# 2019_FDP_PROPULSION.net
KiCad netlist of a schematic drawn in Altium Designer
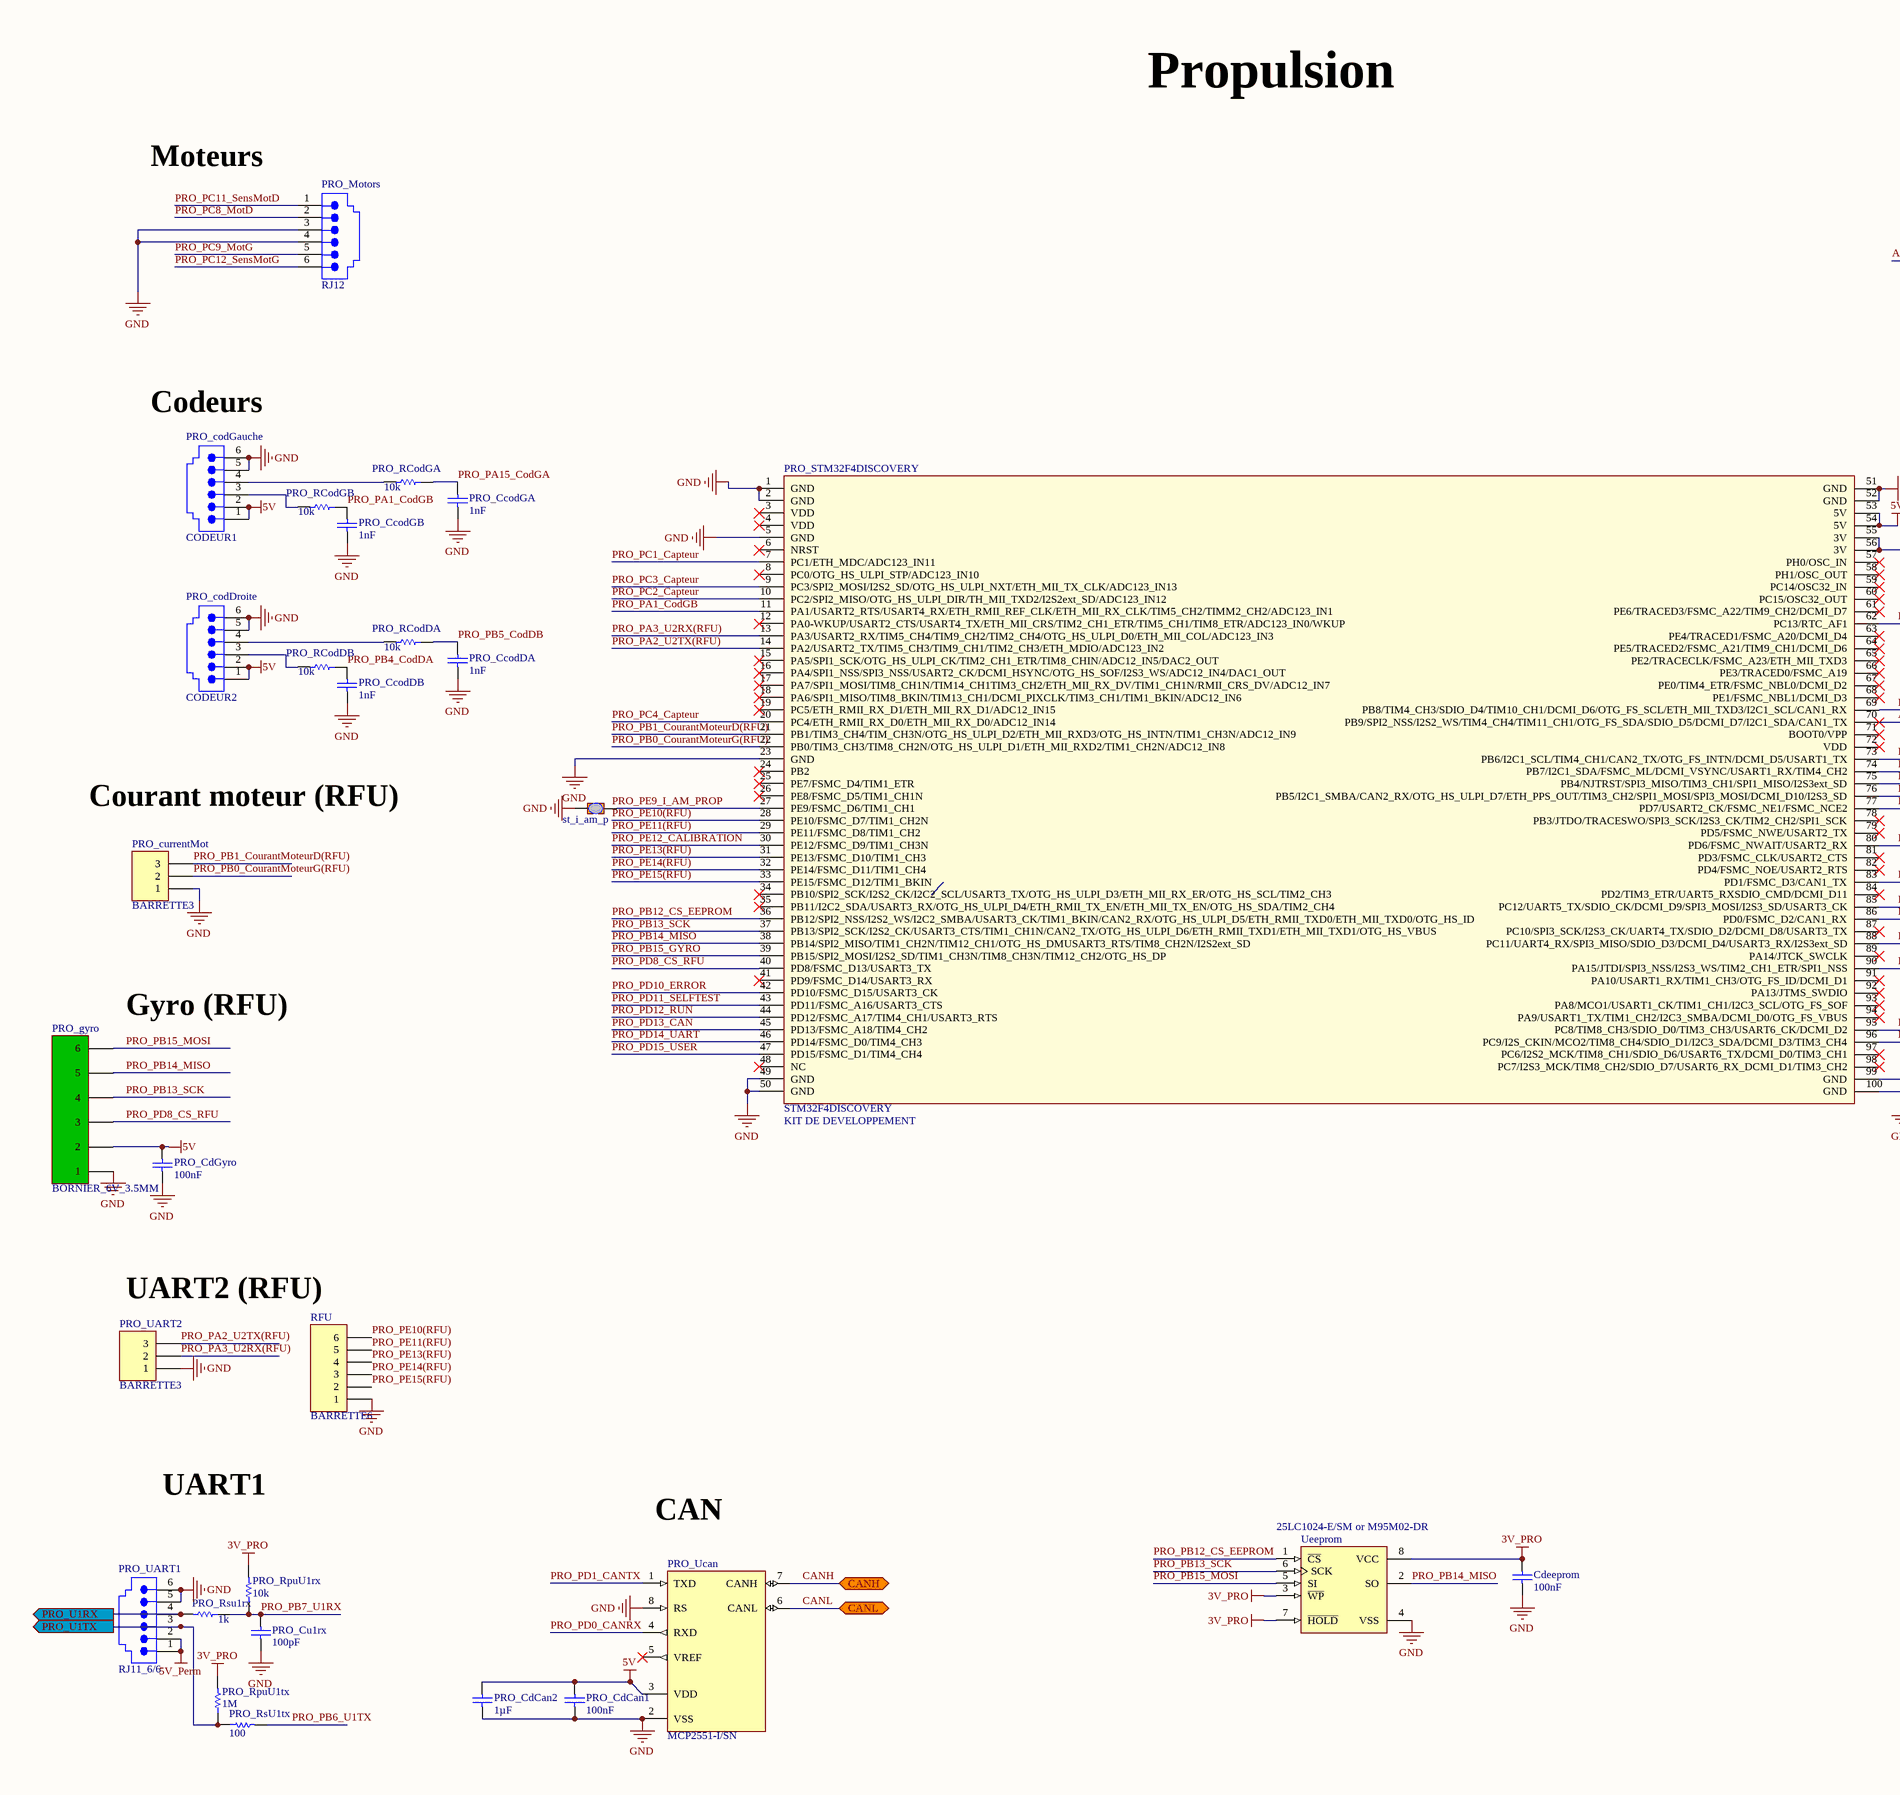
[diagram p0: 2019_FDP_PROPULSION.SchDoc, left]
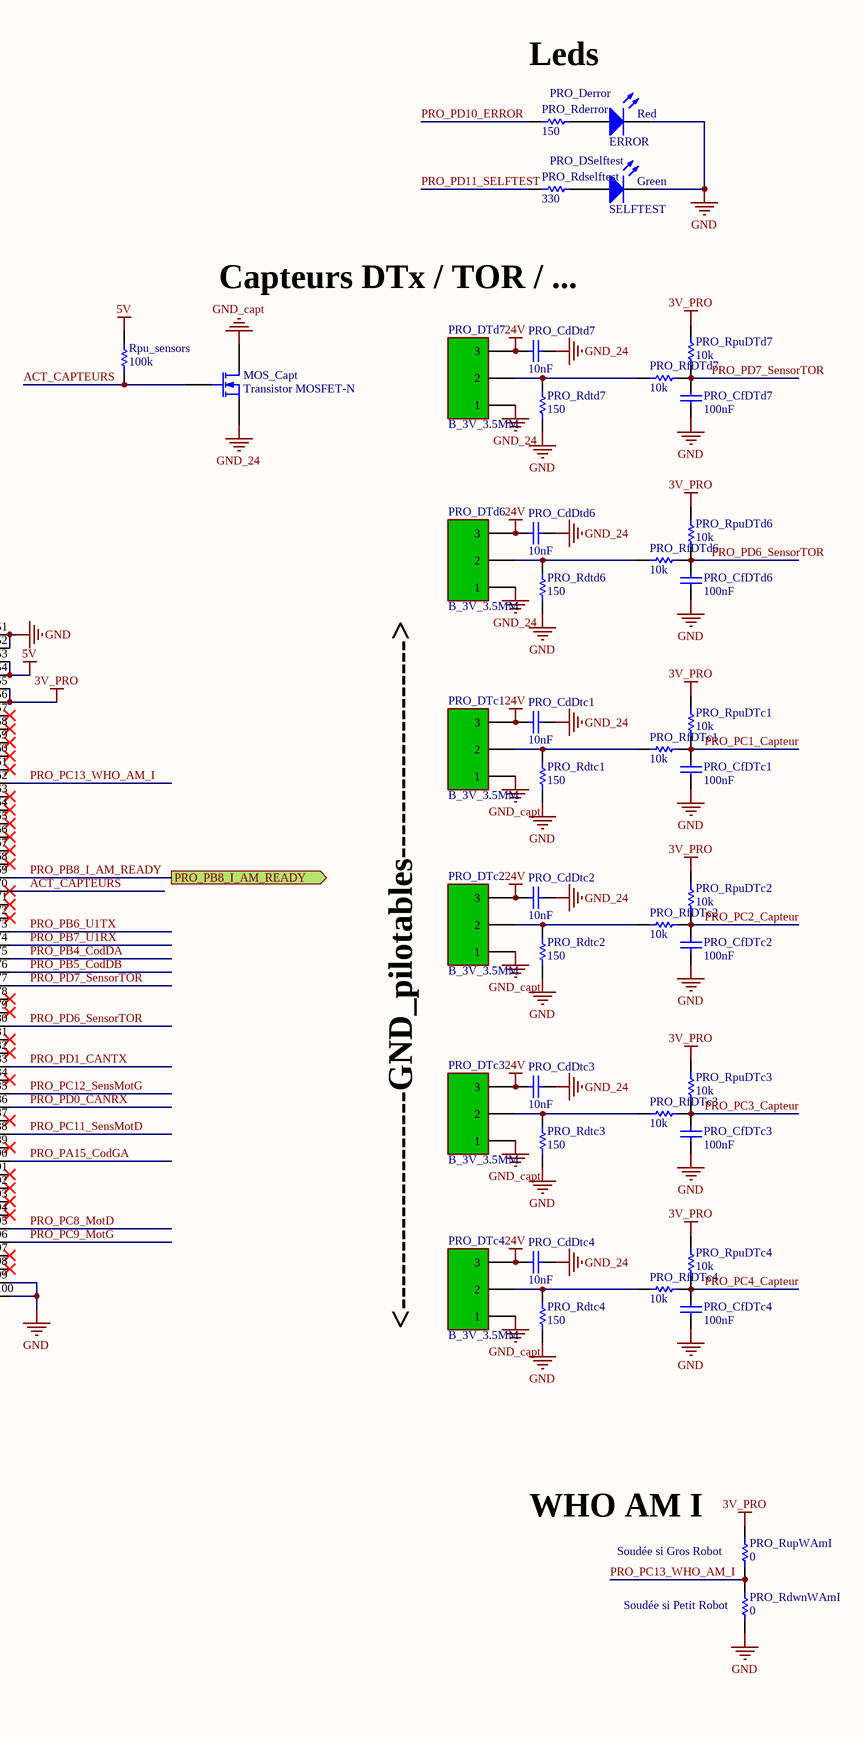
[diagram p1: 2019_FDP_PROPULSION.SchDoc, right]

(export (version "E")
  (design (tool "Eeschema 10.0.6"))
  (components
    (comp (ref "Cdeeprom")
      (value "100nF")
      (footprint "C0805_N")
      (description "Capacitor")
      (fields (field (name "PUBLISHER") "Altium Limited"))
      (libsource (lib "_ROBOT") (part "Condensateur"))
    )
    (comp (ref "MOS_Capt")
      (value "Transistor MOSFET-N")
      (footprint "SOT23-3N")
      (description "N-Channel MOSFET")
      (fields (field (name "PUBLISHER") "Altium Limited"))
      (libsource (lib "_ROBOT") (part "Transistor MOSFET-N"))
    )
    (comp (ref "PRO_CcodDA")
      (value "1nF")
      (footprint "C0805_N")
      (description "Capacitor")
      (fields (field (name "PUBLISHER") "Altium Limited"))
      (libsource (lib "_ROBOT") (part "Condensateur"))
    )
    (comp (ref "PRO_CcodDB")
      (value "1nF")
      (footprint "C0805_N")
      (description "Capacitor")
      (fields (field (name "PUBLISHER") "Altium Limited"))
      (libsource (lib "_ROBOT") (part "Condensateur"))
    )
    (comp (ref "PRO_CcodGA")
      (value "1nF")
      (footprint "C0805_N")
      (description "Capacitor")
      (fields (field (name "PUBLISHER") "Altium Limited"))
      (libsource (lib "_ROBOT") (part "Condensateur"))
    )
    (comp (ref "PRO_CcodGB")
      (value "1nF")
      (footprint "C0805_N")
      (description "Capacitor")
      (fields (field (name "PUBLISHER") "Altium Limited"))
      (libsource (lib "_ROBOT") (part "Condensateur"))
    )
    (comp (ref "PRO_CdCan1")
      (value "100nF")
      (footprint "C0805_N")
      (description "Capacitor")
      (fields (field (name "PUBLISHER") "Altium Limited"))
      (libsource (lib "_ROBOT") (part "Condensateur"))
    )
    (comp (ref "PRO_CdCan2")
      (value "1µF")
      (footprint "C0805_N")
      (description "Capacitor")
      (fields (field (name "PUBLISHER") "Altium Limited"))
      (libsource (lib "_ROBOT") (part "Condensateur"))
    )
    (comp (ref "PRO_CdDtc1")
      (value "10nF")
      (footprint "C0805_N")
      (description "Capacitor")
      (fields (field (name "PUBLISHER") "Altium Limited"))
      (libsource (lib "_ROBOT") (part "Condensateur"))
    )
    (comp (ref "PRO_CdDtc2")
      (value "10nF")
      (footprint "C0805_N")
      (description "Capacitor")
      (fields (field (name "PUBLISHER") "Altium Limited"))
      (libsource (lib "_ROBOT") (part "Condensateur"))
    )
    (comp (ref "PRO_CdDtc3")
      (value "10nF")
      (footprint "C0805_N")
      (description "Capacitor")
      (fields (field (name "PUBLISHER") "Altium Limited"))
      (libsource (lib "_ROBOT") (part "Condensateur"))
    )
    (comp (ref "PRO_CdDtc4")
      (value "10nF")
      (footprint "C0805_N")
      (description "Capacitor")
      (fields (field (name "PUBLISHER") "Altium Limited"))
      (libsource (lib "_ROBOT") (part "Condensateur"))
    )
    (comp (ref "PRO_CdDtd6")
      (value "10nF")
      (footprint "C0805_N")
      (description "Capacitor")
      (fields (field (name "PUBLISHER") "Altium Limited"))
      (libsource (lib "_ROBOT") (part "Condensateur"))
    )
    (comp (ref "PRO_CdDtd7")
      (value "10nF")
      (footprint "C0805_N")
      (description "Capacitor")
      (fields (field (name "PUBLISHER") "Altium Limited"))
      (libsource (lib "_ROBOT") (part "Condensateur"))
    )
    (comp (ref "PRO_CdGyro")
      (value "100nF")
      (footprint "C0805_N")
      (description "Capacitor")
      (fields (field (name "PUBLISHER") "Altium Limited"))
      (libsource (lib "_ROBOT") (part "Condensateur"))
    )
    (comp (ref "PRO_CfDTc1")
      (value "100nF")
      (footprint "C0805_N")
      (description "Capacitor")
      (fields (field (name "PUBLISHER") "Altium Limited"))
      (libsource (lib "_ROBOT") (part "Condensateur"))
    )
    (comp (ref "PRO_CfDTc2")
      (value "100nF")
      (footprint "C0805_N")
      (description "Capacitor")
      (fields (field (name "PUBLISHER") "Altium Limited"))
      (libsource (lib "_ROBOT") (part "Condensateur"))
    )
    (comp (ref "PRO_CfDTc3")
      (value "100nF")
      (footprint "C0805_N")
      (description "Capacitor")
      (fields (field (name "PUBLISHER") "Altium Limited"))
      (libsource (lib "_ROBOT") (part "Condensateur"))
    )
    (comp (ref "PRO_CfDTc4")
      (value "100nF")
      (footprint "C0805_N")
      (description "Capacitor")
      (fields (field (name "PUBLISHER") "Altium Limited"))
      (libsource (lib "_ROBOT") (part "Condensateur"))
    )
    (comp (ref "PRO_CfDTd6")
      (value "100nF")
      (footprint "C0805_N")
      (description "Capacitor")
      (fields (field (name "PUBLISHER") "Altium Limited"))
      (libsource (lib "_ROBOT") (part "Condensateur"))
    )
    (comp (ref "PRO_CfDTd7")
      (value "100nF")
      (footprint "C0805_N")
      (description "Capacitor")
      (fields (field (name "PUBLISHER") "Altium Limited"))
      (libsource (lib "_ROBOT") (part "Condensateur"))
    )
    (comp (ref "PRO_codDroite")
      (value "CODEUR2")
      (footprint "RJ11_6/6 - droit")
      (description "Right Angle, Standard Profile, Offset Latch DECconnect, Flangeless PCB Jack")
      (fields (field (name "PUBLISHER") "Altium Limited"))
      (libsource (lib "miniprojet") (part "RJ11_6/6"))
    )
    (comp (ref "PRO_codGauche")
      (value "CODEUR1")
      (footprint "RJ11_6/6 - droit")
      (description "Right Angle, Standard Profile, Offset Latch DECconnect, Flangeless PCB Jack")
      (fields (field (name "PUBLISHER") "Altium Limited"))
      (libsource (lib "miniprojet") (part "RJ11_6/6"))
    )
    (comp (ref "PRO_Cu1rx")
      (value "100pF")
      (footprint "C0805_N")
      (description "Capacitor")
      (fields (field (name "PUBLISHER") "Altium Limited"))
      (libsource (lib "_ROBOT") (part "Condensateur"))
    )
    (comp (ref "PRO_currentMot")
      (value "BARRETTE3")
      (footprint "HE14_3")
      (description "Header, 3-Pin")
      (fields (field (name "PUBLISHER") "Altium Limited"))
      (libsource (lib "Connecteur") (part "BARRETTE3"))
    )
    (comp (ref "PRO_Derror")
      (value "ERROR")
      (footprint "LED_0805")
      (description "Typical LED")
      (fields (field (name "PUBLISHER") "Altium Limited"))
      (libsource (lib "_ROBOT") (part "LED"))
    )
    (comp (ref "PRO_DSelftest")
      (value "SELFTEST")
      (footprint "LED_0805")
      (description "Typical LED")
      (fields (field (name "PUBLISHER") "Altium Limited"))
      (libsource (lib "_ROBOT") (part "LED"))
    )
    (comp (ref "PRO_DTc1")
      (value "B_3V_3.5MM")
      (footprint "BORNIER_3V_3.5MM")
      (libsource (lib "Connecteur") (part "BORNIER_3V_3.5MM"))
    )
    (comp (ref "PRO_DTc2")
      (value "B_3V_3.5MM")
      (footprint "BORNIER_3V_3.5MM")
      (libsource (lib "Connecteur") (part "BORNIER_3V_3.5MM"))
    )
    (comp (ref "PRO_DTc3")
      (value "B_3V_3.5MM")
      (footprint "BORNIER_3V_3.5MM")
      (libsource (lib "Connecteur") (part "BORNIER_3V_3.5MM"))
    )
    (comp (ref "PRO_DTc4")
      (value "B_3V_3.5MM")
      (footprint "BORNIER_3V_3.5MM")
      (libsource (lib "Connecteur") (part "BORNIER_3V_3.5MM"))
    )
    (comp (ref "PRO_DTd6")
      (value "B_3V_3.5MM")
      (footprint "BORNIER_3V_3.5MM")
      (libsource (lib "Connecteur") (part "BORNIER_3V_3.5MM"))
    )
    (comp (ref "PRO_DTd7")
      (value "B_3V_3.5MM")
      (footprint "BORNIER_3V_3.5MM")
      (libsource (lib "Connecteur") (part "BORNIER_3V_3.5MM"))
    )
    (comp (ref "PRO_gyro")
      (value "BORNIER_6V_3.5MM")
      (footprint "BORNIER_6V_3.5MM")
      (libsource (lib "Connecteur") (part "BORNIER_6V_3.5MM"))
    )
    (comp (ref "PRO_Motors")
      (value "RJ12")
      (footprint "RJ11_6/6 - droit")
      (description "Right Angle, Standard Profile, Offset Latch DECconnect, Flangeless PCB Jack")
      (fields (field (name "PUBLISHER") "Altium Limited"))
      (libsource (lib "Connecteur") (part "RJ11_6/6"))
    )
    (comp (ref "PRO_RCodDA")
      (value "10k")
      (footprint "R1206_N")
      (description "Resistor")
      (fields (field (name "PUBLISHER") "Altium Limited"))
      (libsource (lib "_ROBOT") (part "Resistor"))
    )
    (comp (ref "PRO_RCodDB")
      (value "10k")
      (footprint "R1206_N")
      (description "Resistor")
      (fields (field (name "PUBLISHER") "Altium Limited"))
      (libsource (lib "_ROBOT") (part "Resistor"))
    )
    (comp (ref "PRO_RCodGA")
      (value "10k")
      (footprint "R1206_N")
      (description "Resistor")
      (fields (field (name "PUBLISHER") "Altium Limited"))
      (libsource (lib "_ROBOT") (part "Resistor"))
    )
    (comp (ref "PRO_RCodGB")
      (value "10k")
      (footprint "R1206_N")
      (description "Resistor")
      (fields (field (name "PUBLISHER") "Altium Limited"))
      (libsource (lib "_ROBOT") (part "Resistor"))
    )
    (comp (ref "PRO_Rderror")
      (value "150")
      (footprint "R1206_N")
      (description "Resistor")
      (fields (field (name "PUBLISHER") "Altium Limited"))
      (libsource (lib "_ROBOT") (part "Resistor"))
    )
    (comp (ref "PRO_Rdselftest")
      (value "330")
      (footprint "R1206_N")
      (description "Resistor")
      (fields (field (name "PUBLISHER") "Altium Limited"))
      (libsource (lib "_ROBOT") (part "Resistor"))
    )
    (comp (ref "PRO_Rdtc1")
      (value "150")
      (footprint "R1206_N")
      (description "Resistor")
      (fields (field (name "PUBLISHER") "Altium Limited"))
      (libsource (lib "_ROBOT") (part "Resistor"))
    )
    (comp (ref "PRO_Rdtc2")
      (value "150")
      (footprint "R1206_N")
      (description "Resistor")
      (fields (field (name "PUBLISHER") "Altium Limited"))
      (libsource (lib "_ROBOT") (part "Resistor"))
    )
    (comp (ref "PRO_Rdtc3")
      (value "150")
      (footprint "R1206_N")
      (description "Resistor")
      (fields (field (name "PUBLISHER") "Altium Limited"))
      (libsource (lib "_ROBOT") (part "Resistor"))
    )
    (comp (ref "PRO_Rdtc4")
      (value "150")
      (footprint "R1206_N")
      (description "Resistor")
      (fields (field (name "PUBLISHER") "Altium Limited"))
      (libsource (lib "_ROBOT") (part "Resistor"))
    )
    (comp (ref "PRO_Rdtd6")
      (value "150")
      (footprint "R1206_N")
      (description "Resistor")
      (fields (field (name "PUBLISHER") "Altium Limited"))
      (libsource (lib "_ROBOT") (part "Resistor"))
    )
    (comp (ref "PRO_Rdtd7")
      (value "150")
      (footprint "R1206_N")
      (description "Resistor")
      (fields (field (name "PUBLISHER") "Altium Limited"))
      (libsource (lib "_ROBOT") (part "Resistor"))
    )
    (comp (ref "PRO_RdwnWAmI")
      (value "0")
      (footprint "R1206_N")
      (description "Resistor")
      (fields (field (name "PUBLISHER") "Altium Limited"))
      (libsource (lib "_ROBOT") (part "Resistor"))
    )
    (comp (ref "PRO_RfDTc1")
      (value "10k")
      (footprint "R1206_N")
      (description "Resistor")
      (fields (field (name "PUBLISHER") "Altium Limited"))
      (libsource (lib "_ROBOT") (part "Resistor"))
    )
    (comp (ref "PRO_RfDTc2")
      (value "10k")
      (footprint "R1206_N")
      (description "Resistor")
      (fields (field (name "PUBLISHER") "Altium Limited"))
      (libsource (lib "_ROBOT") (part "Resistor"))
    )
    (comp (ref "PRO_RfDTc3")
      (value "10k")
      (footprint "R1206_N")
      (description "Resistor")
      (fields (field (name "PUBLISHER") "Altium Limited"))
      (libsource (lib "_ROBOT") (part "Resistor"))
    )
    (comp (ref "PRO_RfDTc4")
      (value "10k")
      (footprint "R1206_N")
      (description "Resistor")
      (fields (field (name "PUBLISHER") "Altium Limited"))
      (libsource (lib "_ROBOT") (part "Resistor"))
    )
    (comp (ref "PRO_RfDTd6")
      (value "10k")
      (footprint "R1206_N")
      (description "Resistor")
      (fields (field (name "PUBLISHER") "Altium Limited"))
      (libsource (lib "_ROBOT") (part "Resistor"))
    )
    (comp (ref "PRO_RfDTd7")
      (value "10k")
      (footprint "R1206_N")
      (description "Resistor")
      (fields (field (name "PUBLISHER") "Altium Limited"))
      (libsource (lib "_ROBOT") (part "Resistor"))
    )
    (comp (ref "PRO_RpuDTc1")
      (value "10k")
      (footprint "R1206_N")
      (description "Resistor")
      (fields (field (name "PUBLISHER") "Altium Limited"))
      (libsource (lib "_ROBOT") (part "Resistor"))
    )
    (comp (ref "PRO_RpuDTc2")
      (value "10k")
      (footprint "R1206_N")
      (description "Resistor")
      (fields (field (name "PUBLISHER") "Altium Limited"))
      (libsource (lib "_ROBOT") (part "Resistor"))
    )
    (comp (ref "PRO_RpuDTc3")
      (value "10k")
      (footprint "R1206_N")
      (description "Resistor")
      (fields (field (name "PUBLISHER") "Altium Limited"))
      (libsource (lib "_ROBOT") (part "Resistor"))
    )
    (comp (ref "PRO_RpuDTc4")
      (value "10k")
      (footprint "R1206_N")
      (description "Resistor")
      (fields (field (name "PUBLISHER") "Altium Limited"))
      (libsource (lib "_ROBOT") (part "Resistor"))
    )
    (comp (ref "PRO_RpuDTd6")
      (value "10k")
      (footprint "R1206_N")
      (description "Resistor")
      (fields (field (name "PUBLISHER") "Altium Limited"))
      (libsource (lib "_ROBOT") (part "Resistor"))
    )
    (comp (ref "PRO_RpuDTd7")
      (value "10k")
      (footprint "R1206_N")
      (description "Resistor")
      (fields (field (name "PUBLISHER") "Altium Limited"))
      (libsource (lib "_ROBOT") (part "Resistor"))
    )
    (comp (ref "PRO_RpuU1rx")
      (value "10k")
      (footprint "R1206_N")
      (description "Resistor")
      (fields (field (name "PUBLISHER") "Altium Limited"))
      (libsource (lib "_ROBOT") (part "Resistor"))
    )
    (comp (ref "PRO_RpuU1tx")
      (value "1M")
      (footprint "R1206_N")
      (description "Resistor")
      (fields (field (name "PUBLISHER") "Altium Limited"))
      (libsource (lib "_ROBOT") (part "Resistor"))
    )
    (comp (ref "PRO_Rsu1rx")
      (value "1k")
      (footprint "R1206_N")
      (description "Resistor")
      (fields (field (name "PUBLISHER") "Altium Limited"))
      (libsource (lib "_ROBOT") (part "Resistor"))
    )
    (comp (ref "PRO_RsU1tx")
      (value "100")
      (footprint "R1206_N")
      (description "Resistor")
      (fields (field (name "PUBLISHER") "Altium Limited"))
      (libsource (lib "_ROBOT") (part "Resistor"))
    )
    (comp (ref "PRO_RupWAmI")
      (value "0")
      (footprint "R1206_N")
      (description "Resistor")
      (fields (field (name "PUBLISHER") "Altium Limited"))
      (libsource (lib "_ROBOT") (part "Resistor"))
    )
    (comp (ref "PRO_STM32F4DISCOVERY")
      (value "STM32F4DISCOVERY")
      (footprint "STM32_F4DISCOVERY")
      (description "KIT DE DEVELOPPEMENT POUR MICROCONTROLEUR STM32F407VGT6")
      (fields (field (name "TYPE") "KIT DE DEVELOPPEMENT"))
      (libsource (lib "circuits integres") (part "STM32F4DISCOVERY"))
    )
    (comp (ref "PRO_UART1")
      (value "RJ11_6/6")
      (footprint "RJ11_6/6 - droit")
      (description "Right Angle, Standard Profile, Offset Latch DECconnect, Flangeless PCB Jack")
      (fields (field (name "PUBLISHER") "Altium Limited"))
      (libsource (lib "Connecteur") (part "RJ11_6/6"))
    )
    (comp (ref "PRO_UART2")
      (value "BARRETTE3")
      (footprint "HE14_3")
      (description "Header, 3-Pin")
      (fields (field (name "PUBLISHER") "Altium Limited"))
      (libsource (lib "Connecteur") (part "BARRETTE3"))
    )
    (comp (ref "PRO_Ucan")
      (value "MCP2551-I/SN")
      (footprint "SO8_N")
      (description "High-Speed CAN Transceiver, 8-Pin SOIC, Industrial Temperature")
      (fields (field (name "PUBLISHER") "Damien Guitton"))
      (libsource (lib "Circuit intégré") (part "MCP2551-I/SN"))
    )
    (comp (ref "RFU")
      (value "BARRETTE6")
      (footprint "HE14_6")
      (description "Header, 6-Pin")
      (fields (field (name "PUBLISHER") "Altium Limited"))
      (libsource (lib "Connecteur") (part "BARRETTE6"))
    )
    (comp (ref "Rpu_sensors")
      (value "100k")
      (footprint "R1206_N")
      (description "Resistor")
      (fields (field (name "PUBLISHER") "Altium Limited"))
      (libsource (lib "_ROBOT") (part "Resistor"))
    )
    (comp (ref "st_i_am_p")
      (value "Goutte Strap_2")
      (footprint "Goutte Strap_2 Pads_Clearance 0.254mm")
      (fields (field (name "PUBLISHER") "Damien Guitton"))
      (libsource (lib "DG_Connecteur") (part "Goutte Strap_2"))
    )
    (comp (ref "Ueeprom")
      (value "25LC1024-E/SM or M95M02-DR")
      (footprint "SOIJ-SM8_N")
      (description "1 Mbit SPI Bus Serial EEPROM, 8-Pin SOIC, Extended Temperature")
      (fields (field (name "MANUFACTURER") "Microchip") (field (name "PARTNUMBER") "25LC1024-E/SM"))
      (libsource (lib "Microchip SPI Serial EEPROM") (part "25LC1024-E/SM"))
    )
  )
  (nets
    (net (code "1") (name "/ACT_CAPTEURS") (class "Default")
      (node (ref "MOS_Capt") (pin "1") (pinfunction "G_1") (pintype "passive"))
      (node (ref "PRO_STM32F4DISCOVERY") (pin "70") (pinfunction "PB9/SPI2_NSS/I2S2_WS/TIM4_CH4/TIM11_CH1/OTG_FS_SDA/SDIO_D5/DCMI_D7/I2C1_SDA/CAN1_TX_70") (pintype "passive"))
      (node (ref "Rpu_sensors") (pin "1") (pinfunction "1_1") (pintype "passive"))
    )
    (net (code "2") (name "/CANH") (class "Default")
      (node (ref "PRO_Ucan") (pin "7") (pinfunction "CANH_7") (pintype "bidirectional"))
    )
    (net (code "3") (name "/CANL") (class "Default")
      (node (ref "PRO_Ucan") (pin "6") (pinfunction "CANL_6") (pintype "bidirectional"))
    )
    (net (code "4") (name "/PRO_PA1_CodGB") (class "Default")
      (node (ref "PRO_CcodGB") (pin "2") (pinfunction "2_2") (pintype "passive"))
      (node (ref "PRO_RCodGB") (pin "1") (pinfunction "1_1") (pintype "passive"))
      (node (ref "PRO_STM32F4DISCOVERY") (pin "11") (pinfunction "PA1/USART2_RTS/USART4_RX/ETH_RMII_REF_CLK/ETH_MII_RX_CLK/TIM5_CH2/TIMM2_CH2/ADC123_IN1_11") (pintype "passive"))
    )
    (net (code "5") (name "/PRO_PA2_U2TX(RFU)") (class "Default")
      (node (ref "PRO_STM32F4DISCOVERY") (pin "14") (pinfunction "PA2/USART2_TX/TIM5_CH3/TIM9_CH1/TIM2_CH3/ETH_MDIO/ADC123_IN2_14") (pintype "passive"))
      (node (ref "PRO_UART2") (pin "3") (pinfunction "3_3") (pintype "passive"))
    )
    (net (code "6") (name "/PRO_PA3_U2RX(RFU)") (class "Default")
      (node (ref "PRO_STM32F4DISCOVERY") (pin "13") (pinfunction "PA3/USART2_RX/TIM5_CH4/TIM9_CH2/TIM2_CH4/OTG_HS_ULPI_D0/ETH_MII_COL/ADC123_IN3_13") (pintype "passive"))
      (node (ref "PRO_UART2") (pin "2") (pinfunction "2_2") (pintype "passive"))
    )
    (net (code "7") (name "/PRO_PA15_CodGA") (class "Default")
      (node (ref "PRO_CcodGA") (pin "2") (pinfunction "2_2") (pintype "passive"))
      (node (ref "PRO_RCodGA") (pin "1") (pinfunction "1_1") (pintype "passive"))
      (node (ref "PRO_STM32F4DISCOVERY") (pin "90") (pinfunction "PA15/JTDI/SPI3_NSS/I2S3_WS/TIM2_CH1_ETR/SPI1_NSS_90") (pintype "passive"))
    )
    (net (code "8") (name "/PRO_PB0_CourantMoteurG(RFU)") (class "Default")
      (node (ref "PRO_STM32F4DISCOVERY") (pin "22") (pinfunction "PB0/TIM3_CH3/TIM8_CH2N/OTG_HS_ULPI_D1/ETH_MII_RXD2/TIM1_CH2N/ADC12_IN8_22") (pintype "passive"))
      (node (ref "PRO_currentMot") (pin "2") (pinfunction "2_2") (pintype "passive"))
    )
    (net (code "9") (name "/PRO_PB1_CourantMoteurD(RFU)") (class "Default")
      (node (ref "PRO_STM32F4DISCOVERY") (pin "21") (pinfunction "PB1/TIM3_CH4/TIM_CH3N/OTG_HS_ULPI_D2/ETH_MII_RXD3/OTG_HS_INTN/TIM1_CH3N/ADC12_IN9_21") (pintype "passive"))
      (node (ref "PRO_currentMot") (pin "3") (pinfunction "3_3") (pintype "passive"))
    )
    (net (code "10") (name "/PRO_PB4_CodDA") (class "Default")
      (node (ref "PRO_CcodDB") (pin "2") (pinfunction "2_2") (pintype "passive"))
      (node (ref "PRO_RCodDB") (pin "1") (pinfunction "1_1") (pintype "passive"))
      (node (ref "PRO_STM32F4DISCOVERY") (pin "75") (pinfunction "PB4/NJTRST/SPI3_MISO/TIM3_CH1/SPI1_MISO/I2S3ext_SD_75") (pintype "passive"))
    )
    (net (code "11") (name "/PRO_PB5_CodDB") (class "Default")
      (node (ref "PRO_CcodDA") (pin "2") (pinfunction "2_2") (pintype "passive"))
      (node (ref "PRO_RCodDA") (pin "1") (pinfunction "1_1") (pintype "passive"))
      (node (ref "PRO_STM32F4DISCOVERY") (pin "76") (pinfunction "PB5/I2C1_SMBA/CAN2_RX/OTG_HS_ULPI_D7/ETH_PPS_OUT/TIM3_CH2/SPI1_MOSI/SPI3_MOSI/DCMI_D10/I2S3_SD_76") (pintype "passive"))
    )
    (net (code "12") (name "/PRO_PB6_U1TX") (class "Default")
      (node (ref "PRO_RsU1tx") (pin "2") (pinfunction "2_2") (pintype "passive"))
      (node (ref "PRO_STM32F4DISCOVERY") (pin "73") (pinfunction "PB6/I2C1_SCL/TIM4_CH1/CAN2_TX/OTG_FS_INTN/DCMI_D5/USART1_TX_73") (pintype "passive"))
    )
    (net (code "13") (name "/PRO_PB7_U1RX") (class "Default")
      (node (ref "PRO_Cu1rx") (pin "2") (pinfunction "2_2") (pintype "passive"))
      (node (ref "PRO_RpuU1rx") (pin "1") (pinfunction "1_1") (pintype "passive"))
      (node (ref "PRO_Rsu1rx") (pin "1") (pinfunction "1_1") (pintype "passive"))
      (node (ref "PRO_STM32F4DISCOVERY") (pin "74") (pinfunction "PB7/I2C1_SDA/FSMC_ML/DCMI_VSYNC/USART1_RX/TIM4_CH2_74") (pintype "passive"))
    )
    (net (code "14") (name "/PRO_PB8_I_AM_READY") (class "Default")
      (node (ref "PRO_STM32F4DISCOVERY") (pin "69") (pinfunction "PB8/TIM4_CH3/SDIO_D4/TIM10_CH1/DCMI_D6/OTG_FS_SCL/ETH_MII_TXD3/I2C1_SCL/CAN1_RX_69") (pintype "passive"))
    )
    (net (code "15") (name "/PRO_PB12_CS_EEPROM") (class "Default")
      (node (ref "PRO_STM32F4DISCOVERY") (pin "36") (pinfunction "PB12/SPI2_NSS/I2S2_WS/I2C2_SMBA/USART3_CK/TIM1_BKIN/CAN2_RX/OTG_HS_ULPI_D5/ETH_RMII_TXD0/ETH_MII_TXD0/OTG_HS_ID_36") (pintype "passive"))
      (node (ref "Ueeprom") (pin "1") (pinfunction "~{CS}_1") (pintype "input"))
    )
    (net (code "16") (name "/PRO_PB13_SCK") (class "Default")
      (node (ref "PRO_STM32F4DISCOVERY") (pin "37") (pinfunction "PB13/SPI2_SCK/I2S2_CK/USART3_CTS/TIM1_CH1N/CAN2_TX/OTG_HS_ULPI_D6/ETH_RMII_TXD1/ETH_MII_TXD1/OTG_HS_VBUS_37") (pintype "passive"))
      (node (ref "PRO_gyro") (pin "4") (pinfunction "4_4") (pintype "passive"))
      (node (ref "Ueeprom") (pin "6") (pinfunction "SCK_6") (pintype "input"))
    )
    (net (code "17") (name "/PRO_PB14_MISO") (class "Default")
      (node (ref "PRO_STM32F4DISCOVERY") (pin "38") (pinfunction "PB14/SPI2_MISO/TIM1_CH2N/TIM12_CH1/OTG_HS_DMUSART3_RTS/TIM8_CH2N/I2S2ext_SD_38") (pintype "passive"))
      (node (ref "PRO_gyro") (pin "5") (pinfunction "5_5") (pintype "passive"))
      (node (ref "Ueeprom") (pin "2") (pinfunction "SO_2") (pintype "tri_state"))
    )
    (net (code "18") (name "/PRO_PB15_GYRO") (class "Default")
      (node (ref "PRO_STM32F4DISCOVERY") (pin "39") (pinfunction "PB15/SPI2_MOSI/I2S2_SD/TIM1_CH3N/TIM8_CH3N/TIM12_CH2/OTG_HS_DP_39") (pintype "passive"))
    )
    (net (code "19") (name "/PRO_PB15_MOSI") (class "Default")
      (node (ref "PRO_gyro") (pin "6") (pinfunction "6_6") (pintype "passive"))
      (node (ref "Ueeprom") (pin "5") (pinfunction "SI_5") (pintype "input"))
    )
    (net (code "20") (name "/PRO_PC1_Capteur") (class "Default")
      (node (ref "PRO_CfDTc1") (pin "2") (pinfunction "2_2") (pintype "passive"))
      (node (ref "PRO_RfDTc1") (pin "2") (pinfunction "2_2") (pintype "passive"))
      (node (ref "PRO_RpuDTc1") (pin "1") (pinfunction "1_1") (pintype "passive"))
      (node (ref "PRO_STM32F4DISCOVERY") (pin "7") (pinfunction "PC1/ETH_MDC/ADC123_IN11_7") (pintype "passive"))
    )
    (net (code "21") (name "/PRO_PC2_Capteur") (class "Default")
      (node (ref "PRO_CfDTc2") (pin "2") (pinfunction "2_2") (pintype "passive"))
      (node (ref "PRO_RfDTc2") (pin "2") (pinfunction "2_2") (pintype "passive"))
      (node (ref "PRO_RpuDTc2") (pin "1") (pinfunction "1_1") (pintype "passive"))
      (node (ref "PRO_STM32F4DISCOVERY") (pin "10") (pinfunction "PC2/SPI2_MISO/OTG_HS_ULPI_DIR/TH_MII_TXD2/I2S2ext_SD/ADC123_IN12_10") (pintype "passive"))
    )
    (net (code "22") (name "/PRO_PC3_Capteur") (class "Default")
      (node (ref "PRO_CfDTc3") (pin "2") (pinfunction "2_2") (pintype "passive"))
      (node (ref "PRO_RfDTc3") (pin "2") (pinfunction "2_2") (pintype "passive"))
      (node (ref "PRO_RpuDTc3") (pin "1") (pinfunction "1_1") (pintype "passive"))
      (node (ref "PRO_STM32F4DISCOVERY") (pin "9") (pinfunction "PC3/SPI2_MOSI/I2S2_SD/OTG_HS_ULPI_NXT/ETH_MII_TX_CLK/ADC123_IN13_9") (pintype "passive"))
    )
    (net (code "23") (name "/PRO_PC4_Capteur") (class "Default")
      (node (ref "PRO_CfDTc4") (pin "2") (pinfunction "2_2") (pintype "passive"))
      (node (ref "PRO_RfDTc4") (pin "2") (pinfunction "2_2") (pintype "passive"))
      (node (ref "PRO_RpuDTc4") (pin "1") (pinfunction "1_1") (pintype "passive"))
      (node (ref "PRO_STM32F4DISCOVERY") (pin "20") (pinfunction "PC4/ETH_RMII_RX_D0/ETH_MII_RX_D0/ADC12_IN14_20") (pintype "passive"))
    )
    (net (code "24") (name "/PRO_PC8_MotD") (class "Default")
      (node (ref "PRO_Motors") (pin "2") (pinfunction "2_2") (pintype "passive"))
      (node (ref "PRO_STM32F4DISCOVERY") (pin "95") (pinfunction "PC8/TIM8_CH3/SDIO_D0/TIM3_CH3/USART6_CK/DCMI_D2_95") (pintype "passive"))
    )
    (net (code "25") (name "/PRO_PC9_MotG") (class "Default")
      (node (ref "PRO_Motors") (pin "5") (pinfunction "5_5") (pintype "passive"))
      (node (ref "PRO_STM32F4DISCOVERY") (pin "96") (pinfunction "PC9/I2S_CKIN/MCO2/TIM8_CH4/SDIO_D1/I2C3_SDA/DCMI_D3/TIM3_CH4_96") (pintype "passive"))
    )
    (net (code "26") (name "/PRO_PC11_SensMotD") (class "Default")
      (node (ref "PRO_Motors") (pin "1") (pinfunction "1_1") (pintype "passive"))
      (node (ref "PRO_STM32F4DISCOVERY") (pin "88") (pinfunction "PC11/UART4_RX/SPI3_MISO/SDIO_D3/DCMI_D4/USART3_RX/I2S3ext_SD_88") (pintype "passive"))
    )
    (net (code "27") (name "/PRO_PC12_SensMotG") (class "Default")
      (node (ref "PRO_Motors") (pin "6") (pinfunction "6_6") (pintype "passive"))
      (node (ref "PRO_STM32F4DISCOVERY") (pin "85") (pinfunction "PC12/UART5_TX/SDIO_CK/DCMI_D9/SPI3_MOSI/I2S3_SD/USART3_CK_85") (pintype "passive"))
    )
    (net (code "28") (name "/PRO_PC13_WHO_AM_I") (class "Default")
      (node (ref "PRO_RdwnWAmI") (pin "2") (pinfunction "2_2") (pintype "passive"))
      (node (ref "PRO_RupWAmI") (pin "1") (pinfunction "1_1") (pintype "passive"))
      (node (ref "PRO_STM32F4DISCOVERY") (pin "62") (pinfunction "PC13/RTC_AF1_62") (pintype "passive"))
    )
    (net (code "29") (name "/PRO_PD0_CANRX") (class "Default")
      (node (ref "PRO_STM32F4DISCOVERY") (pin "86") (pinfunction "PD0/FSMC_D2/CAN1_RX_86") (pintype "passive"))
      (node (ref "PRO_Ucan") (pin "4") (pinfunction "RXD_4") (pintype "output"))
    )
    (net (code "30") (name "/PRO_PD1_CANTX") (class "Default")
      (node (ref "PRO_STM32F4DISCOVERY") (pin "83") (pinfunction "PD1/FSMC_D3/CAN1_TX_83") (pintype "passive"))
      (node (ref "PRO_Ucan") (pin "1") (pinfunction "TXD_1") (pintype "input"))
    )
    (net (code "31") (name "/PRO_PD6_SensorTOR") (class "Default")
      (node (ref "PRO_CfDTd6") (pin "2") (pinfunction "2_2") (pintype "passive"))
      (node (ref "PRO_RfDTd6") (pin "2") (pinfunction "2_2") (pintype "passive"))
      (node (ref "PRO_RpuDTd6") (pin "1") (pinfunction "1_1") (pintype "passive"))
      (node (ref "PRO_STM32F4DISCOVERY") (pin "80") (pinfunction "PD6/FSMC_NWAIT/USART2_RX_80") (pintype "passive"))
    )
    (net (code "32") (name "/PRO_PD7_SensorTOR") (class "Default")
      (node (ref "PRO_CfDTd7") (pin "2") (pinfunction "2_2") (pintype "passive"))
      (node (ref "PRO_RfDTd7") (pin "2") (pinfunction "2_2") (pintype "passive"))
      (node (ref "PRO_RpuDTd7") (pin "1") (pinfunction "1_1") (pintype "passive"))
      (node (ref "PRO_STM32F4DISCOVERY") (pin "77") (pinfunction "PD7/USART2_CK/FSMC_NE1/FSMC_NCE2_77") (pintype "passive"))
    )
    (net (code "33") (name "/PRO_PD8_CS_RFU") (class "Default")
      (node (ref "PRO_STM32F4DISCOVERY") (pin "40") (pinfunction "PD8/FSMC_D13/USART3_TX_40") (pintype "passive"))
      (node (ref "PRO_gyro") (pin "3") (pinfunction "3_3") (pintype "passive"))
    )
    (net (code "34") (name "/PRO_PD10_ERROR") (class "Default")
      (node (ref "PRO_Rderror") (pin "1") (pinfunction "1_1") (pintype "passive"))
      (node (ref "PRO_STM32F4DISCOVERY") (pin "42") (pinfunction "PD10/FSMC_D15/USART3_CK_42") (pintype "passive"))
    )
    (net (code "35") (name "/PRO_PD11_SELFTEST") (class "Default")
      (node (ref "PRO_Rdselftest") (pin "1") (pinfunction "1_1") (pintype "passive"))
      (node (ref "PRO_STM32F4DISCOVERY") (pin "43") (pinfunction "PD11/FSMC_A16/USART3_CTS_43") (pintype "passive"))
    )
    (net (code "36") (name "/PRO_PD12_RUN") (class "Default")
      (node (ref "PRO_STM32F4DISCOVERY") (pin "44") (pinfunction "PD12/FSMC_A17/TIM4_CH1/USART3_RTS_44") (pintype "passive"))
    )
    (net (code "37") (name "/PRO_PD13_CAN") (class "Default")
      (node (ref "PRO_STM32F4DISCOVERY") (pin "45") (pinfunction "PD13/FSMC_A18/TIM4_CH2_45") (pintype "passive"))
    )
    (net (code "38") (name "/PRO_PD14_UART") (class "Default")
      (node (ref "PRO_STM32F4DISCOVERY") (pin "46") (pinfunction "PD14/FSMC_D0/TIM4_CH3_46") (pintype "passive"))
    )
    (net (code "39") (name "/PRO_PD15_USER") (class "Default")
      (node (ref "PRO_STM32F4DISCOVERY") (pin "47") (pinfunction "PD15/FSMC_D1/TIM4_CH4_47") (pintype "passive"))
    )
    (net (code "41") (name "/PRO_PE10(RFU)") (class "Default")
      (node (ref "PRO_STM32F4DISCOVERY") (pin "28") (pinfunction "PE10/FSMC_D7/TIM1_CH2N_28") (pintype "passive"))
      (node (ref "RFU") (pin "6") (pinfunction "6_6") (pintype "passive"))
    )
    (net (code "42") (name "/PRO_PE11(RFU)") (class "Default")
      (node (ref "PRO_STM32F4DISCOVERY") (pin "29") (pinfunction "PE11/FSMC_D8/TIM1_CH2_29") (pintype "passive"))
      (node (ref "RFU") (pin "5") (pinfunction "5_5") (pintype "passive"))
    )
    (net (code "43") (name "/PRO_PE12_CALIBRATION") (class "Default")
      (node (ref "PRO_STM32F4DISCOVERY") (pin "30") (pinfunction "PE12/FSMC_D9/TIM1_CH3N_30") (pintype "passive"))
    )
    (net (code "44") (name "/PRO_PE13(RFU)") (class "Default")
      (node (ref "PRO_STM32F4DISCOVERY") (pin "31") (pinfunction "PE13/FSMC_D10/TIM1_CH3_31") (pintype "passive"))
      (node (ref "RFU") (pin "4") (pinfunction "4_4") (pintype "passive"))
    )
    (net (code "45") (name "/PRO_PE14(RFU)") (class "Default")
      (node (ref "PRO_STM32F4DISCOVERY") (pin "32") (pinfunction "PE14/FSMC_D11/TIM1_CH4_32") (pintype "passive"))
      (node (ref "RFU") (pin "3") (pinfunction "3_3") (pintype "passive"))
    )
    (net (code "46") (name "/PRO_PE15(RFU)") (class "Default")
      (node (ref "PRO_STM32F4DISCOVERY") (pin "33") (pinfunction "PE15/FSMC_D12/TIM1_BKIN_33") (pintype "passive"))
      (node (ref "RFU") (pin "2") (pinfunction "2_2") (pintype "passive"))
    )
    (net (code "47") (name "/PRO_U1RX") (class "Default")
      (node (ref "PRO_Rsu1rx") (pin "2") (pinfunction "2_2") (pintype "passive"))
      (node (ref "PRO_UART1") (pin "4") (pinfunction "4_4") (pintype "passive"))
    )
    (net (code "48") (name "/PRO_U1TX") (class "Default")
      (node (ref "PRO_RpuU1tx") (pin "1") (pinfunction "1_1") (pintype "passive"))
      (node (ref "PRO_RsU1tx") (pin "1") (pinfunction "1_1") (pintype "passive"))
      (node (ref "PRO_UART1") (pin "3") (pinfunction "3_3") (pintype "passive"))
    )
    (net (code "49") (name "3V_PRO") (class "Default")
      (node (ref "Cdeeprom") (pin "2") (pinfunction "2_2") (pintype "passive"))
      (node (ref "PRO_RpuDTc1") (pin "2") (pinfunction "2_2") (pintype "passive"))
      (node (ref "PRO_RpuDTc2") (pin "2") (pinfunction "2_2") (pintype "passive"))
      (node (ref "PRO_RpuDTc3") (pin "2") (pinfunction "2_2") (pintype "passive"))
      (node (ref "PRO_RpuDTc4") (pin "2") (pinfunction "2_2") (pintype "passive"))
      (node (ref "PRO_RpuDTd6") (pin "2") (pinfunction "2_2") (pintype "passive"))
      (node (ref "PRO_RpuDTd7") (pin "2") (pinfunction "2_2") (pintype "passive"))
      (node (ref "PRO_RpuU1rx") (pin "2") (pinfunction "2_2") (pintype "passive"))
      (node (ref "PRO_RpuU1tx") (pin "2") (pinfunction "2_2") (pintype "passive"))
      (node (ref "PRO_RupWAmI") (pin "2") (pinfunction "2_2") (pintype "passive"))
      (node (ref "PRO_STM32F4DISCOVERY") (pin "55") (pinfunction "3V_55") (pintype "passive"))
      (node (ref "PRO_STM32F4DISCOVERY") (pin "56") (pinfunction "3V_56") (pintype "passive"))
      (node (ref "Ueeprom") (pin "3") (pinfunction "~{WP}_3") (pintype "input"))
      (node (ref "Ueeprom") (pin "7") (pinfunction "~{HOLD}_7") (pintype "input"))
      (node (ref "Ueeprom") (pin "8") (pinfunction "VCC_8") (pintype "power_in"))
    )
    (net (code "50") (name "5V") (class "Default")
      (node (ref "PRO_CdCan1") (pin "2") (pinfunction "2_2") (pintype "passive"))
      (node (ref "PRO_CdCan2") (pin "2") (pinfunction "2_2") (pintype "passive"))
      (node (ref "PRO_CdGyro") (pin "2") (pinfunction "2_2") (pintype "passive"))
      (node (ref "PRO_STM32F4DISCOVERY") (pin "53") (pinfunction "5V_53") (pintype "passive"))
      (node (ref "PRO_STM32F4DISCOVERY") (pin "54") (pinfunction "5V_54") (pintype "passive"))
      (node (ref "PRO_Ucan") (pin "3") (pinfunction "VDD_3") (pintype "power_in"))
      (node (ref "PRO_codDroite") (pin "1") (pinfunction "1_1") (pintype "passive"))
      (node (ref "PRO_codDroite") (pin "2") (pinfunction "2_2") (pintype "passive"))
      (node (ref "PRO_codGauche") (pin "1") (pinfunction "1_1") (pintype "passive"))
      (node (ref "PRO_codGauche") (pin "2") (pinfunction "2_2") (pintype "passive"))
      (node (ref "PRO_gyro") (pin "2") (pinfunction "2_2") (pintype "passive"))
      (node (ref "Rpu_sensors") (pin "2") (pinfunction "2_2") (pintype "passive"))
    )
    (net (code "51") (name "5V_Perm") (class "Default")
      (node (ref "PRO_UART1") (pin "1") (pinfunction "1_1") (pintype "passive"))
      (node (ref "PRO_UART1") (pin "2") (pinfunction "2_2") (pintype "passive"))
    )
    (net (code "52") (name "24V") (class "Default")
      (node (ref "PRO_CdDtc1") (pin "2") (pinfunction "2_2") (pintype "passive"))
      (node (ref "PRO_CdDtc2") (pin "2") (pinfunction "2_2") (pintype "passive"))
      (node (ref "PRO_CdDtc3") (pin "2") (pinfunction "2_2") (pintype "passive"))
      (node (ref "PRO_CdDtc4") (pin "2") (pinfunction "2_2") (pintype "passive"))
      (node (ref "PRO_CdDtd6") (pin "2") (pinfunction "2_2") (pintype "passive"))
      (node (ref "PRO_CdDtd7") (pin "2") (pinfunction "2_2") (pintype "passive"))
      (node (ref "PRO_DTc1") (pin "3") (pinfunction "3_3") (pintype "passive"))
      (node (ref "PRO_DTc2") (pin "3") (pinfunction "3_3") (pintype "passive"))
      (node (ref "PRO_DTc3") (pin "3") (pinfunction "3_3") (pintype "passive"))
      (node (ref "PRO_DTc4") (pin "3") (pinfunction "3_3") (pintype "passive"))
      (node (ref "PRO_DTd6") (pin "3") (pinfunction "3_3") (pintype "passive"))
      (node (ref "PRO_DTd7") (pin "3") (pinfunction "3_3") (pintype "passive"))
    )
    (net (code "53") (name "GND") (class "Default")
      (node (ref "Cdeeprom") (pin "1") (pinfunction "1_1") (pintype "passive"))
      (node (ref "PRO_CcodDA") (pin "1") (pinfunction "1_1") (pintype "passive"))
      (node (ref "PRO_CcodDB") (pin "1") (pinfunction "1_1") (pintype "passive"))
      (node (ref "PRO_CcodGA") (pin "1") (pinfunction "1_1") (pintype "passive"))
      (node (ref "PRO_CcodGB") (pin "1") (pinfunction "1_1") (pintype "passive"))
      (node (ref "PRO_CdCan1") (pin "1") (pinfunction "1_1") (pintype "passive"))
      (node (ref "PRO_CdCan2") (pin "1") (pinfunction "1_1") (pintype "passive"))
      (node (ref "PRO_CdGyro") (pin "1") (pinfunction "1_1") (pintype "passive"))
      (node (ref "PRO_CfDTc1") (pin "1") (pinfunction "1_1") (pintype "passive"))
      (node (ref "PRO_CfDTc2") (pin "1") (pinfunction "1_1") (pintype "passive"))
      (node (ref "PRO_CfDTc3") (pin "1") (pinfunction "1_1") (pintype "passive"))
      (node (ref "PRO_CfDTc4") (pin "1") (pinfunction "1_1") (pintype "passive"))
      (node (ref "PRO_CfDTd6") (pin "1") (pinfunction "1_1") (pintype "passive"))
      (node (ref "PRO_CfDTd7") (pin "1") (pinfunction "1_1") (pintype "passive"))
      (node (ref "PRO_Cu1rx") (pin "1") (pinfunction "1_1") (pintype "passive"))
      (node (ref "PRO_DSelftest") (pin "2") (pinfunction "K_2") (pintype "passive"))
      (node (ref "PRO_Derror") (pin "2") (pinfunction "K_2") (pintype "passive"))
      (node (ref "PRO_Motors") (pin "3") (pinfunction "3_3") (pintype "passive"))
      (node (ref "PRO_Motors") (pin "4") (pinfunction "4_4") (pintype "passive"))
      (node (ref "PRO_Rdtc1") (pin "1") (pinfunction "1_1") (pintype "passive"))
      (node (ref "PRO_Rdtc2") (pin "1") (pinfunction "1_1") (pintype "passive"))
      (node (ref "PRO_Rdtc3") (pin "1") (pinfunction "1_1") (pintype "passive"))
      (node (ref "PRO_Rdtc4") (pin "1") (pinfunction "1_1") (pintype "passive"))
      (node (ref "PRO_Rdtd6") (pin "1") (pinfunction "1_1") (pintype "passive"))
      (node (ref "PRO_Rdtd7") (pin "1") (pinfunction "1_1") (pintype "passive"))
      (node (ref "PRO_RdwnWAmI") (pin "1") (pinfunction "1_1") (pintype "passive"))
      (node (ref "PRO_STM32F4DISCOVERY") (pin "1") (pinfunction "GND_1") (pintype "passive"))
      (node (ref "PRO_STM32F4DISCOVERY") (pin "100") (pinfunction "GND_100") (pintype "passive"))
      (node (ref "PRO_STM32F4DISCOVERY") (pin "2") (pinfunction "GND_2") (pintype "passive"))
      (node (ref "PRO_STM32F4DISCOVERY") (pin "23") (pinfunction "GND_23") (pintype "passive"))
      (node (ref "PRO_STM32F4DISCOVERY") (pin "49") (pinfunction "GND_49") (pintype "passive"))
      (node (ref "PRO_STM32F4DISCOVERY") (pin "5") (pinfunction "GND_5") (pintype "passive"))
      (node (ref "PRO_STM32F4DISCOVERY") (pin "50") (pinfunction "GND_50") (pintype "passive"))
      (node (ref "PRO_STM32F4DISCOVERY") (pin "51") (pinfunction "GND_51") (pintype "passive"))
      (node (ref "PRO_STM32F4DISCOVERY") (pin "52") (pinfunction "GND_52") (pintype "passive"))
      (node (ref "PRO_STM32F4DISCOVERY") (pin "99") (pinfunction "GND_99") (pintype "passive"))
      (node (ref "PRO_UART1") (pin "5") (pinfunction "5_5") (pintype "passive"))
      (node (ref "PRO_UART1") (pin "6") (pinfunction "6_6") (pintype "passive"))
      (node (ref "PRO_UART2") (pin "1") (pinfunction "1_1") (pintype "passive"))
      (node (ref "PRO_Ucan") (pin "2") (pinfunction "VSS_2") (pintype "power_in"))
      (node (ref "PRO_Ucan") (pin "8") (pinfunction "RS_8") (pintype "input"))
      (node (ref "PRO_codDroite") (pin "5") (pinfunction "5_5") (pintype "passive"))
      (node (ref "PRO_codDroite") (pin "6") (pinfunction "6_6") (pintype "passive"))
      (node (ref "PRO_codGauche") (pin "5") (pinfunction "5_5") (pintype "passive"))
      (node (ref "PRO_codGauche") (pin "6") (pinfunction "6_6") (pintype "passive"))
      (node (ref "PRO_currentMot") (pin "1") (pinfunction "1_1") (pintype "passive"))
      (node (ref "PRO_gyro") (pin "1") (pinfunction "1_1") (pintype "passive"))
      (node (ref "RFU") (pin "1") (pinfunction "1_1") (pintype "passive"))
      (node (ref "Ueeprom") (pin "4") (pinfunction "VSS_4") (pintype "power_in"))
      (node (ref "st_i_am_p") (pin "1") (pinfunction "1_1") (pintype "passive"))
    )
    (net (code "54") (name "GND_24") (class "Default")
      (node (ref "MOS_Capt") (pin "2") (pinfunction "S_2") (pintype "passive"))
      (node (ref "PRO_CdDtc1") (pin "1") (pinfunction "1_1") (pintype "passive"))
      (node (ref "PRO_CdDtc2") (pin "1") (pinfunction "1_1") (pintype "passive"))
      (node (ref "PRO_CdDtc3") (pin "1") (pinfunction "1_1") (pintype "passive"))
      (node (ref "PRO_CdDtc4") (pin "1") (pinfunction "1_1") (pintype "passive"))
      (node (ref "PRO_CdDtd6") (pin "1") (pinfunction "1_1") (pintype "passive"))
      (node (ref "PRO_CdDtd7") (pin "1") (pinfunction "1_1") (pintype "passive"))
      (node (ref "PRO_DTd6") (pin "1") (pinfunction "1_1") (pintype "passive"))
      (node (ref "PRO_DTd7") (pin "1") (pinfunction "1_1") (pintype "passive"))
    )
    (net (code "55") (name "GND_capt") (class "Default")
      (node (ref "MOS_Capt") (pin "3") (pinfunction "D_3") (pintype "passive"))
      (node (ref "PRO_DTc1") (pin "1") (pinfunction "1_1") (pintype "passive"))
      (node (ref "PRO_DTc2") (pin "1") (pinfunction "1_1") (pintype "passive"))
      (node (ref "PRO_DTc3") (pin "1") (pinfunction "1_1") (pintype "passive"))
      (node (ref "PRO_DTc4") (pin "1") (pinfunction "1_1") (pintype "passive"))
    )
    (net (code "56") (name "Net-(PRO_DSelftest-A)") (class "Default")
      (node (ref "PRO_DSelftest") (pin "1") (pinfunction "A_1") (pintype "passive"))
      (node (ref "PRO_Rdselftest") (pin "2") (pinfunction "2_2") (pintype "passive"))
    )
    (net (code "57") (name "Net-(PRO_DTc1-Pad2)") (class "Default")
      (node (ref "PRO_DTc1") (pin "2") (pinfunction "2_2") (pintype "passive"))
      (node (ref "PRO_Rdtc1") (pin "2") (pinfunction "2_2") (pintype "passive"))
      (node (ref "PRO_RfDTc1") (pin "1") (pinfunction "1_1") (pintype "passive"))
    )
    (net (code "58") (name "Net-(PRO_DTc2-Pad2)") (class "Default")
      (node (ref "PRO_DTc2") (pin "2") (pinfunction "2_2") (pintype "passive"))
      (node (ref "PRO_Rdtc2") (pin "2") (pinfunction "2_2") (pintype "passive"))
      (node (ref "PRO_RfDTc2") (pin "1") (pinfunction "1_1") (pintype "passive"))
    )
    (net (code "59") (name "Net-(PRO_DTc3-Pad2)") (class "Default")
      (node (ref "PRO_DTc3") (pin "2") (pinfunction "2_2") (pintype "passive"))
      (node (ref "PRO_Rdtc3") (pin "2") (pinfunction "2_2") (pintype "passive"))
      (node (ref "PRO_RfDTc3") (pin "1") (pinfunction "1_1") (pintype "passive"))
    )
    (net (code "60") (name "Net-(PRO_DTc4-Pad2)") (class "Default")
      (node (ref "PRO_DTc4") (pin "2") (pinfunction "2_2") (pintype "passive"))
      (node (ref "PRO_Rdtc4") (pin "2") (pinfunction "2_2") (pintype "passive"))
      (node (ref "PRO_RfDTc4") (pin "1") (pinfunction "1_1") (pintype "passive"))
    )
    (net (code "61") (name "Net-(PRO_DTd6-Pad2)") (class "Default")
      (node (ref "PRO_DTd6") (pin "2") (pinfunction "2_2") (pintype "passive"))
      (node (ref "PRO_Rdtd6") (pin "2") (pinfunction "2_2") (pintype "passive"))
      (node (ref "PRO_RfDTd6") (pin "1") (pinfunction "1_1") (pintype "passive"))
    )
    (net (code "62") (name "Net-(PRO_DTd7-Pad2)") (class "Default")
      (node (ref "PRO_DTd7") (pin "2") (pinfunction "2_2") (pintype "passive"))
      (node (ref "PRO_Rdtd7") (pin "2") (pinfunction "2_2") (pintype "passive"))
      (node (ref "PRO_RfDTd7") (pin "1") (pinfunction "1_1") (pintype "passive"))
    )
    (net (code "63") (name "Net-(PRO_Derror-A)") (class "Default")
      (node (ref "PRO_Derror") (pin "1") (pinfunction "A_1") (pintype "passive"))
      (node (ref "PRO_Rderror") (pin "2") (pinfunction "2_2") (pintype "passive"))
    )
    (net (code "64") (name "Net-(PRO_RCodDA-Pad2)") (class "Default")
      (node (ref "PRO_RCodDA") (pin "2") (pinfunction "2_2") (pintype "passive"))
      (node (ref "PRO_codDroite") (pin "4") (pinfunction "4_4") (pintype "passive"))
    )
    (net (code "65") (name "Net-(PRO_RCodDB-Pad2)") (class "Default")
      (node (ref "PRO_RCodDB") (pin "2") (pinfunction "2_2") (pintype "passive"))
      (node (ref "PRO_codDroite") (pin "3") (pinfunction "3_3") (pintype "passive"))
    )
    (net (code "66") (name "Net-(PRO_RCodGA-Pad2)") (class "Default")
      (node (ref "PRO_RCodGA") (pin "2") (pinfunction "2_2") (pintype "passive"))
      (node (ref "PRO_codGauche") (pin "4") (pinfunction "4_4") (pintype "passive"))
    )
    (net (code "67") (name "Net-(PRO_RCodGB-Pad2)") (class "Default")
      (node (ref "PRO_RCodGB") (pin "2") (pinfunction "2_2") (pintype "passive"))
      (node (ref "PRO_codGauche") (pin "3") (pinfunction "3_3") (pintype "passive"))
    )
    (net (code "68") (name "Net-(PRO_STM32F4DISCOVERY-PE9{slash}FSMC_D6{slash}TIM1_CH1)") (class "Default")
      (node (ref "PRO_STM32F4DISCOVERY") (pin "27") (pinfunction "PE9/FSMC_D6/TIM1_CH1_27") (pintype "passive"))
      (node (ref "st_i_am_p") (pin "2") (pinfunction "2_2") (pintype "passive"))
    )
    (net (code "69") (name "unconnected-(PRO_STM32F4DISCOVERY-BOOT0{slash}VPP-Pad71)") (class "Default")
      (node (ref "PRO_STM32F4DISCOVERY") (pin "71") (pinfunction "BOOT0/VPP_71") (pintype "passive+no_connect"))
    )
    (net (code "70") (name "unconnected-(PRO_STM32F4DISCOVERY-NC-Pad48)") (class "Default")
      (node (ref "PRO_STM32F4DISCOVERY") (pin "48") (pinfunction "NC_48") (pintype "passive+no_connect"))
    )
    (net (code "71") (name "unconnected-(PRO_STM32F4DISCOVERY-NRST-Pad6)") (class "Default")
      (node (ref "PRO_STM32F4DISCOVERY") (pin "6") (pinfunction "NRST_6") (pintype "passive+no_connect"))
    )
    (net (code "72") (name "unconnected-(PRO_STM32F4DISCOVERY-PA0-WKUP{slash}USART2_CTS{slash}USART4_TX{slash}ETH_MII_CRS{slash}TIM2_CH1_ETR{slash}TIM5_CH1{slash}TIM8_ETR{slash}ADC123_IN0{slash}WKUP-Pad12)") (class "Default")
      (node (ref "PRO_STM32F4DISCOVERY") (pin "12") (pinfunction "PA0-WKUP/USART2_CTS/USART4_TX/ETH_MII_CRS/TIM2_CH1_ETR/TIM5_CH1/TIM8_ETR/ADC123_IN0/WKUP_12") (pintype "passive+no_connect"))
    )
    (net (code "73") (name "unconnected-(PRO_STM32F4DISCOVERY-PA4{slash}SPI1_NSS{slash}SPI3_NSS{slash}USART2_CK{slash}DCMI_HSYNC{slash}OTG_HS_SOF{slash}I2S3_WS{slash}ADC12_IN4{slash}DAC1_OUT-Pad16)") (class "Default")
      (node (ref "PRO_STM32F4DISCOVERY") (pin "16") (pinfunction "PA4/SPI1_NSS/SPI3_NSS/USART2_CK/DCMI_HSYNC/OTG_HS_SOF/I2S3_WS/ADC12_IN4/DAC1_OUT_16") (pintype "passive+no_connect"))
    )
    (net (code "74") (name "unconnected-(PRO_STM32F4DISCOVERY-PA5{slash}SPI1_SCK{slash}OTG_HS_ULPI_CK{slash}TIM2_CH1_ETR{slash}TIM8_CHIN{slash}ADC12_IN5{slash}DAC2_OUT-Pad15)") (class "Default")
      (node (ref "PRO_STM32F4DISCOVERY") (pin "15") (pinfunction "PA5/SPI1_SCK/OTG_HS_ULPI_CK/TIM2_CH1_ETR/TIM8_CHIN/ADC12_IN5/DAC2_OUT_15") (pintype "passive+no_connect"))
    )
    (net (code "75") (name "unconnected-(PRO_STM32F4DISCOVERY-PA6{slash}SPI1_MISO{slash}TIM8_BKIN{slash}TIM13_CH1{slash}DCMI_PIXCLK{slash}TIM3_CH1{slash}TIM1_BKIN{slash}ADC12_IN6-Pad18)") (class "Default")
      (node (ref "PRO_STM32F4DISCOVERY") (pin "18") (pinfunction "PA6/SPI1_MISO/TIM8_BKIN/TIM13_CH1/DCMI_PIXCLK/TIM3_CH1/TIM1_BKIN/ADC12_IN6_18") (pintype "passive+no_connect"))
    )
    (net (code "76") (name "unconnected-(PRO_STM32F4DISCOVERY-PA7{slash}SPI1_MOSI{slash}TIM8_CH1N{slash}TIM14_CH1TIM3_CH2{slash}ETH_MII_RX_DV{slash}TIM1_CH1N{slash}RMII_CRS_DV{slash}ADC12_IN7-Pad17)") (class "Default")
      (node (ref "PRO_STM32F4DISCOVERY") (pin "17") (pinfunction "PA7/SPI1_MOSI/TIM8_CH1N/TIM14_CH1TIM3_CH2/ETH_MII_RX_DV/TIM1_CH1N/RMII_CRS_DV/ADC12_IN7_17") (pintype "passive+no_connect"))
    )
    (net (code "77") (name "unconnected-(PRO_STM32F4DISCOVERY-PA8{slash}MCO1{slash}USART1_CK{slash}TIM1_CH1{slash}I2C3_SCL{slash}OTG_FS_SOF-Pad93)") (class "Default")
      (node (ref "PRO_STM32F4DISCOVERY") (pin "93") (pinfunction "PA8/MCO1/USART1_CK/TIM1_CH1/I2C3_SCL/OTG_FS_SOF_93") (pintype "passive+no_connect"))
    )
    (net (code "78") (name "unconnected-(PRO_STM32F4DISCOVERY-PA9{slash}USART1_TX{slash}TIM1_CH2{slash}I2C3_SMBA{slash}DCMI_D0{slash}OTG_FS_VBUS-Pad94)") (class "Default")
      (node (ref "PRO_STM32F4DISCOVERY") (pin "94") (pinfunction "PA9/USART1_TX/TIM1_CH2/I2C3_SMBA/DCMI_D0/OTG_FS_VBUS_94") (pintype "passive+no_connect"))
    )
    (net (code "79") (name "unconnected-(PRO_STM32F4DISCOVERY-PA10{slash}USART1_RX{slash}TIM1_CH3{slash}OTG_FS_ID{slash}DCMI_D1-Pad91)") (class "Default")
      (node (ref "PRO_STM32F4DISCOVERY") (pin "91") (pinfunction "PA10/USART1_RX/TIM1_CH3/OTG_FS_ID/DCMI_D1_91") (pintype "passive+no_connect"))
    )
    (net (code "80") (name "unconnected-(PRO_STM32F4DISCOVERY-PA13{slash}JTMS_SWDIO-Pad92)") (class "Default")
      (node (ref "PRO_STM32F4DISCOVERY") (pin "92") (pinfunction "PA13/JTMS_SWDIO_92") (pintype "passive+no_connect"))
    )
    (net (code "81") (name "unconnected-(PRO_STM32F4DISCOVERY-PA14{slash}JTCK_SWCLK-Pad89)") (class "Default")
      (node (ref "PRO_STM32F4DISCOVERY") (pin "89") (pinfunction "PA14/JTCK_SWCLK_89") (pintype "passive+no_connect"))
    )
    (net (code "82") (name "unconnected-(PRO_STM32F4DISCOVERY-PB2-Pad24)") (class "Default")
      (node (ref "PRO_STM32F4DISCOVERY") (pin "24") (pinfunction "PB2_24") (pintype "passive+no_connect"))
    )
    (net (code "83") (name "unconnected-(PRO_STM32F4DISCOVERY-PB3{slash}JTDO{slash}TRACESWO{slash}SPI3_SCK{slash}I2S3_CK{slash}TIM2_CH2{slash}SPI1_SCK-Pad78)") (class "Default")
      (node (ref "PRO_STM32F4DISCOVERY") (pin "78") (pinfunction "PB3/JTDO/TRACESWO/SPI3_SCK/I2S3_CK/TIM2_CH2/SPI1_SCK_78") (pintype "passive+no_connect"))
    )
    (net (code "84") (name "unconnected-(PRO_STM32F4DISCOVERY-PB10{slash}SPI2_SCK{slash}I2S2_CK{slash}I2C2_SCL{slash}USART3_TX{slash}OTG_HS_ULPI_D3{slash}ETH_MII_RX_ER{slash}OTG_HS_SCL{slash}TIM2_CH3-Pad34)") (class "Default")
      (node (ref "PRO_STM32F4DISCOVERY") (pin "34") (pinfunction "PB10/SPI2_SCK/I2S2_CK/I2C2_SCL/USART3_TX/OTG_HS_ULPI_D3/ETH_MII_RX_ER/OTG_HS_SCL/TIM2_CH3_34") (pintype "passive+no_connect"))
    )
    (net (code "85") (name "unconnected-(PRO_STM32F4DISCOVERY-PB11{slash}I2C2_SDA{slash}USART3_RX{slash}OTG_HS_ULPI_D4{slash}ETH_RMII_TX_EN{slash}ETH_MII_TX_EN{slash}OTG_HS_SDA{slash}TIM2_CH4-Pad35)") (class "Default")
      (node (ref "PRO_STM32F4DISCOVERY") (pin "35") (pinfunction "PB11/I2C2_SDA/USART3_RX/OTG_HS_ULPI_D4/ETH_RMII_TX_EN/ETH_MII_TX_EN/OTG_HS_SDA/TIM2_CH4_35") (pintype "passive+no_connect"))
    )
    (net (code "86") (name "unconnected-(PRO_STM32F4DISCOVERY-PC0{slash}OTG_HS_ULPI_STP{slash}ADC123_IN10-Pad8)") (class "Default")
      (node (ref "PRO_STM32F4DISCOVERY") (pin "8") (pinfunction "PC0/OTG_HS_ULPI_STP/ADC123_IN10_8") (pintype "passive+no_connect"))
    )
    (net (code "87") (name "unconnected-(PRO_STM32F4DISCOVERY-PC5{slash}ETH_RMII_RX_D1{slash}ETH_MII_RX_D1{slash}ADC12_IN15-Pad19)") (class "Default")
      (node (ref "PRO_STM32F4DISCOVERY") (pin "19") (pinfunction "PC5/ETH_RMII_RX_D1/ETH_MII_RX_D1/ADC12_IN15_19") (pintype "passive+no_connect"))
    )
    (net (code "88") (name "unconnected-(PRO_STM32F4DISCOVERY-PC6{slash}I2S2_MCK{slash}TIM8_CH1{slash}SDIO_D6{slash}USART6_TX{slash}DCMI_D0{slash}TIM3_CH1-Pad97)") (class "Default")
      (node (ref "PRO_STM32F4DISCOVERY") (pin "97") (pinfunction "PC6/I2S2_MCK/TIM8_CH1/SDIO_D6/USART6_TX/DCMI_D0/TIM3_CH1_97") (pintype "passive+no_connect"))
    )
    (net (code "89") (name "unconnected-(PRO_STM32F4DISCOVERY-PC7{slash}I2S3_MCK{slash}TIM8_CH2{slash}SDIO_D7{slash}USART6_RX_DCMI_D1{slash}TIM3_CH2-Pad98)") (class "Default")
      (node (ref "PRO_STM32F4DISCOVERY") (pin "98") (pinfunction "PC7/I2S3_MCK/TIM8_CH2/SDIO_D7/USART6_RX_DCMI_D1/TIM3_CH2_98") (pintype "passive+no_connect"))
    )
    (net (code "90") (name "unconnected-(PRO_STM32F4DISCOVERY-PC10{slash}SPI3_SCK{slash}I2S3_CK{slash}UART4_TX{slash}SDIO_D2{slash}DCMI_D8{slash}USART3_TX-Pad87)") (class "Default")
      (node (ref "PRO_STM32F4DISCOVERY") (pin "87") (pinfunction "PC10/SPI3_SCK/I2S3_CK/UART4_TX/SDIO_D2/DCMI_D8/USART3_TX_87") (pintype "passive+no_connect"))
    )
    (net (code "91") (name "unconnected-(PRO_STM32F4DISCOVERY-PC14{slash}OSC32_IN-Pad59)") (class "Default")
      (node (ref "PRO_STM32F4DISCOVERY") (pin "59") (pinfunction "PC14/OSC32_IN_59") (pintype "passive+no_connect"))
    )
    (net (code "92") (name "unconnected-(PRO_STM32F4DISCOVERY-PC15{slash}OSC32_OUT-Pad60)") (class "Default")
      (node (ref "PRO_STM32F4DISCOVERY") (pin "60") (pinfunction "PC15/OSC32_OUT_60") (pintype "passive+no_connect"))
    )
    (net (code "93") (name "unconnected-(PRO_STM32F4DISCOVERY-PD2{slash}TIM3_ETR{slash}UART5_RXSDIO_CMD{slash}DCMI_D11-Pad84)") (class "Default")
      (node (ref "PRO_STM32F4DISCOVERY") (pin "84") (pinfunction "PD2/TIM3_ETR/UART5_RXSDIO_CMD/DCMI_D11_84") (pintype "passive+no_connect"))
    )
    (net (code "94") (name "unconnected-(PRO_STM32F4DISCOVERY-PD3{slash}FSMC_CLK{slash}USART2_CTS-Pad81)") (class "Default")
      (node (ref "PRO_STM32F4DISCOVERY") (pin "81") (pinfunction "PD3/FSMC_CLK/USART2_CTS_81") (pintype "passive+no_connect"))
    )
    (net (code "95") (name "unconnected-(PRO_STM32F4DISCOVERY-PD4{slash}FSMC_NOE{slash}USART2_RTS-Pad82)") (class "Default")
      (node (ref "PRO_STM32F4DISCOVERY") (pin "82") (pinfunction "PD4/FSMC_NOE/USART2_RTS_82") (pintype "passive+no_connect"))
    )
    (net (code "96") (name "unconnected-(PRO_STM32F4DISCOVERY-PD5{slash}FSMC_NWE{slash}USART2_TX-Pad79)") (class "Default")
      (node (ref "PRO_STM32F4DISCOVERY") (pin "79") (pinfunction "PD5/FSMC_NWE/USART2_TX_79") (pintype "passive+no_connect"))
    )
    (net (code "97") (name "unconnected-(PRO_STM32F4DISCOVERY-PD9{slash}FSMC_D14{slash}USART3_RX-Pad41)") (class "Default")
      (node (ref "PRO_STM32F4DISCOVERY") (pin "41") (pinfunction "PD9/FSMC_D14/USART3_RX_41") (pintype "passive+no_connect"))
    )
    (net (code "98") (name "unconnected-(PRO_STM32F4DISCOVERY-PE0{slash}TIM4_ETR{slash}FSMC_NBL0{slash}DCMI_D2-Pad67)") (class "Default")
      (node (ref "PRO_STM32F4DISCOVERY") (pin "67") (pinfunction "PE0/TIM4_ETR/FSMC_NBL0/DCMI_D2_67") (pintype "passive+no_connect"))
    )
    (net (code "99") (name "unconnected-(PRO_STM32F4DISCOVERY-PE1{slash}FSMC_NBL1{slash}DCMI_D3-Pad68)") (class "Default")
      (node (ref "PRO_STM32F4DISCOVERY") (pin "68") (pinfunction "PE1/FSMC_NBL1/DCMI_D3_68") (pintype "passive+no_connect"))
    )
    (net (code "100") (name "unconnected-(PRO_STM32F4DISCOVERY-PE2{slash}TRACECLK{slash}FSMC_A23{slash}ETH_MII_TXD3-Pad65)") (class "Default")
      (node (ref "PRO_STM32F4DISCOVERY") (pin "65") (pinfunction "PE2/TRACECLK/FSMC_A23/ETH_MII_TXD3_65") (pintype "passive+no_connect"))
    )
    (net (code "101") (name "unconnected-(PRO_STM32F4DISCOVERY-PE3{slash}TRACED0{slash}FSMC_A19-Pad66)") (class "Default")
      (node (ref "PRO_STM32F4DISCOVERY") (pin "66") (pinfunction "PE3/TRACED0/FSMC_A19_66") (pintype "passive+no_connect"))
    )
    (net (code "102") (name "unconnected-(PRO_STM32F4DISCOVERY-PE4{slash}TRACED1{slash}FSMC_A20{slash}DCMI_D4-Pad63)") (class "Default")
      (node (ref "PRO_STM32F4DISCOVERY") (pin "63") (pinfunction "PE4/TRACED1/FSMC_A20/DCMI_D4_63") (pintype "passive+no_connect"))
    )
    (net (code "103") (name "unconnected-(PRO_STM32F4DISCOVERY-PE5{slash}TRACED2{slash}FSMC_A21{slash}TIM9_CH1{slash}DCMI_D6-Pad64)") (class "Default")
      (node (ref "PRO_STM32F4DISCOVERY") (pin "64") (pinfunction "PE5/TRACED2/FSMC_A21/TIM9_CH1/DCMI_D6_64") (pintype "passive+no_connect"))
    )
    (net (code "104") (name "unconnected-(PRO_STM32F4DISCOVERY-PE6{slash}TRACED3{slash}FSMC_A22{slash}TIM9_CH2{slash}DCMI_D7-Pad61)") (class "Default")
      (node (ref "PRO_STM32F4DISCOVERY") (pin "61") (pinfunction "PE6/TRACED3/FSMC_A22/TIM9_CH2/DCMI_D7_61") (pintype "passive+no_connect"))
    )
    (net (code "105") (name "unconnected-(PRO_STM32F4DISCOVERY-PE7{slash}FSMC_D4{slash}TIM1_ETR-Pad25)") (class "Default")
      (node (ref "PRO_STM32F4DISCOVERY") (pin "25") (pinfunction "PE7/FSMC_D4/TIM1_ETR_25") (pintype "passive+no_connect"))
    )
    (net (code "106") (name "unconnected-(PRO_STM32F4DISCOVERY-PE8{slash}FSMC_D5{slash}TIM1_CH1N-Pad26)") (class "Default")
      (node (ref "PRO_STM32F4DISCOVERY") (pin "26") (pinfunction "PE8/FSMC_D5/TIM1_CH1N_26") (pintype "passive+no_connect"))
    )
    (net (code "107") (name "unconnected-(PRO_STM32F4DISCOVERY-PH0{slash}OSC_IN-Pad57)") (class "Default")
      (node (ref "PRO_STM32F4DISCOVERY") (pin "57") (pinfunction "PH0/OSC_IN_57") (pintype "passive+no_connect"))
    )
    (net (code "108") (name "unconnected-(PRO_STM32F4DISCOVERY-PH1{slash}OSC_OUT-Pad58)") (class "Default")
      (node (ref "PRO_STM32F4DISCOVERY") (pin "58") (pinfunction "PH1/OSC_OUT_58") (pintype "passive+no_connect"))
    )
    (net (code "109") (name "unconnected-(PRO_STM32F4DISCOVERY-VDD-Pad3)") (class "Default")
      (node (ref "PRO_STM32F4DISCOVERY") (pin "3") (pinfunction "VDD_3") (pintype "passive+no_connect"))
    )
    (net (code "110") (name "unconnected-(PRO_STM32F4DISCOVERY-VDD-Pad4)") (class "Default")
      (node (ref "PRO_STM32F4DISCOVERY") (pin "4") (pinfunction "VDD_4") (pintype "passive+no_connect"))
    )
    (net (code "111") (name "unconnected-(PRO_STM32F4DISCOVERY-VDD-Pad72)") (class "Default")
      (node (ref "PRO_STM32F4DISCOVERY") (pin "72") (pinfunction "VDD_72") (pintype "passive+no_connect"))
    )
    (net (code "112") (name "unconnected-(PRO_Ucan-VREF-Pad5)") (class "Default")
      (node (ref "PRO_Ucan") (pin "5") (pinfunction "VREF_5") (pintype "output+no_connect"))
    )
  )
)
